# tiny__THT.net
KiCad netlist of a schematic drawn in EAGLE
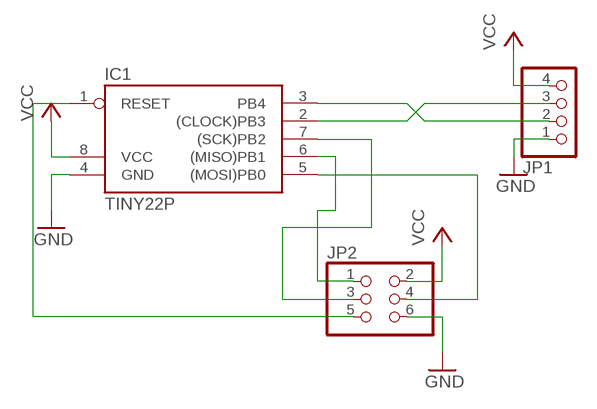
[diagram p0: schematic, sheet 1]

(export (version "E")
  (design (tool "Eeschema 10.0.6"))
  (components
    (comp (ref "IC1")
      (value "TINY22P")
      (footprint "eagle-import:DIL08")
      (libsource (lib "eagle-import") (part "TINY22P"))
    )
    (comp (ref "JP1")
      (value "PINHD-1X4")
      (footprint "eagle-import:1X04")
      (libsource (lib "eagle-import") (part "PINHD-1X4"))
    )
    (comp (ref "JP2")
      (value "PINHD-2X3")
      (footprint "eagle-import:2X03")
      (libsource (lib "eagle-import") (part "PINHD-2X3"))
    )
  )
  (nets
    (net (code "1") (name "GND") (class "Default")
      (node (ref "IC1") (pin "4") (pinfunction "GND_4") (pintype "power_in"))
      (node (ref "JP1") (pin "1") (pinfunction "1_1") (pintype "passive"))
      (node (ref "JP2") (pin "6") (pinfunction "6_6") (pintype "passive"))
    )
    (net (code "2") (name "Net-(IC1-(CLOCK)PB3)") (class "Default")
      (node (ref "IC1") (pin "2") (pinfunction "(CLOCK)PB3_2") (pintype "bidirectional"))
      (node (ref "JP1") (pin "3") (pinfunction "3_3") (pintype "passive"))
    )
    (net (code "3") (name "Net-(IC1-(MISO)PB1)") (class "Default")
      (node (ref "IC1") (pin "6") (pinfunction "(MISO)PB1_6") (pintype "bidirectional"))
      (node (ref "JP2") (pin "1") (pinfunction "1_1") (pintype "passive"))
    )
    (net (code "4") (name "Net-(IC1-(MOSI)PB0)") (class "Default")
      (node (ref "IC1") (pin "5") (pinfunction "(MOSI)PB0_5") (pintype "bidirectional"))
      (node (ref "JP2") (pin "4") (pinfunction "4_4") (pintype "passive"))
    )
    (net (code "5") (name "Net-(IC1-(SCK)PB2)") (class "Default")
      (node (ref "IC1") (pin "7") (pinfunction "(SCK)PB2_7") (pintype "bidirectional"))
      (node (ref "JP2") (pin "3") (pinfunction "3_3") (pintype "passive"))
    )
    (net (code "6") (name "Net-(IC1-PB4)") (class "Default")
      (node (ref "IC1") (pin "3") (pinfunction "PB4_3") (pintype "bidirectional"))
      (node (ref "JP1") (pin "2") (pinfunction "2_2") (pintype "passive"))
    )
    (net (code "7") (name "Net-(IC1-RESET)") (class "Default")
      (node (ref "IC1") (pin "1") (pinfunction "RESET_1") (pintype "input"))
      (node (ref "JP2") (pin "5") (pinfunction "5_5") (pintype "passive"))
    )
    (net (code "8") (name "VCC") (class "Default")
      (node (ref "IC1") (pin "8") (pinfunction "VCC_8") (pintype "power_in"))
      (node (ref "JP1") (pin "4") (pinfunction "4_4") (pintype "passive"))
      (node (ref "JP2") (pin "2") (pinfunction "2_2") (pintype "passive"))
    )
  )
)
